# FPGA_DAC.net
KiCad netlist of a schematic drawn in Altium Designer
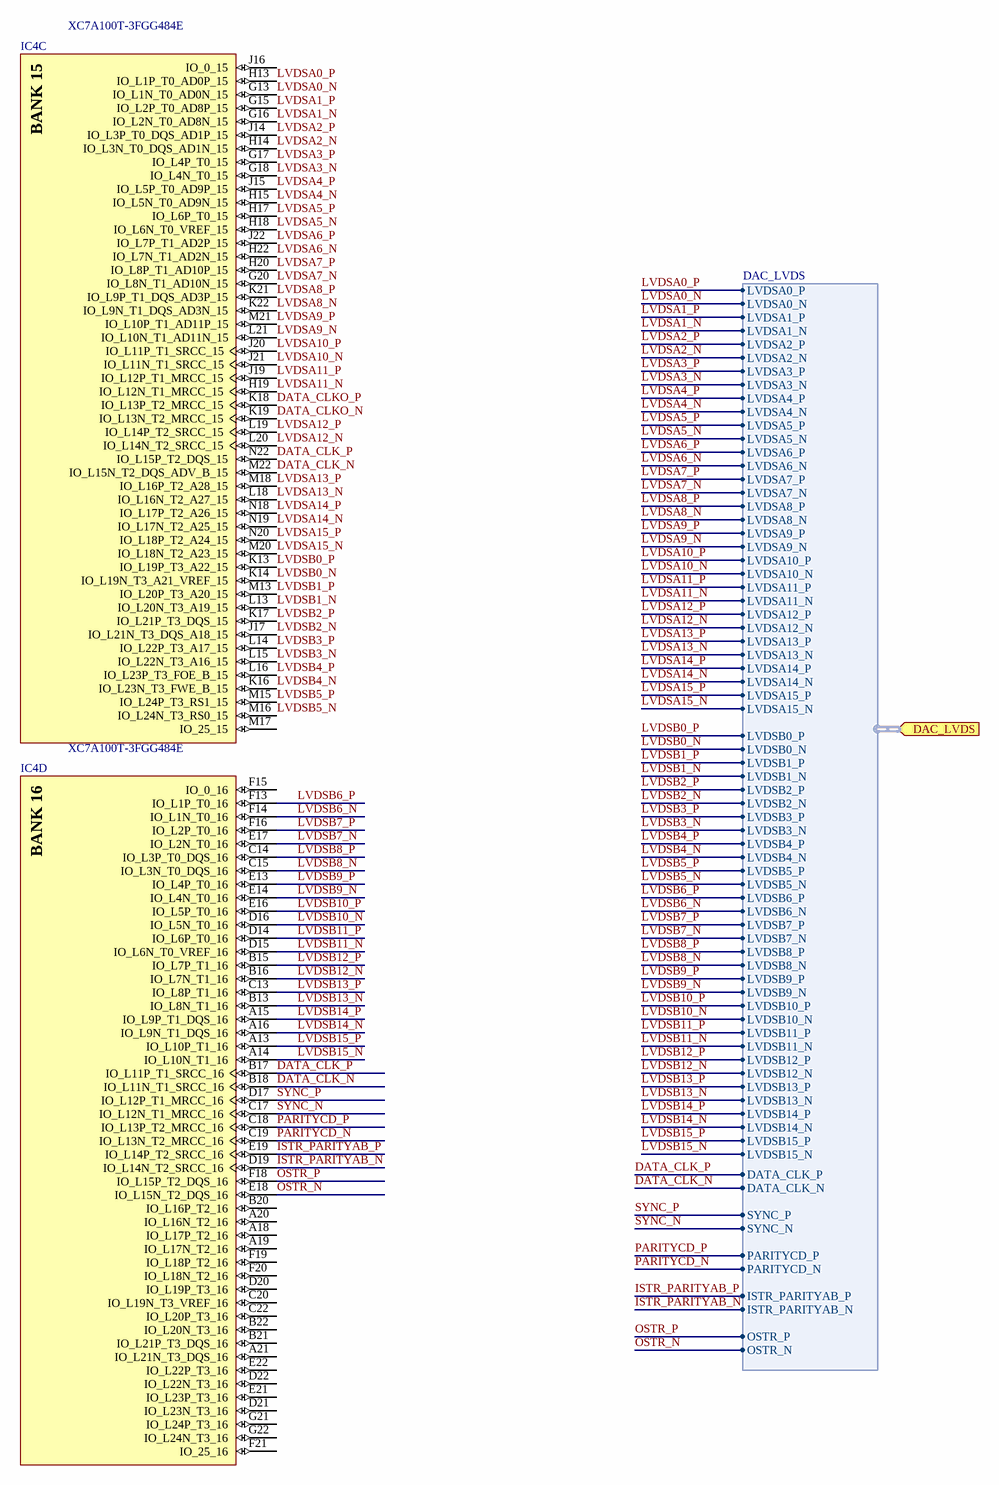
[diagram p0: FPGA_DAC.SchDoc]

(export (version "E")
  (design (tool "Eeschema 10.0.6"))
  (components
    (comp (ref "IC4")
      (value "XC7A100T-3FGG484E")
      (footprint "FGG484")
      (description "Artix-7 FPGA, 285 User I/Os, 4 GTP, 484-Ball BGA, Speed Grade 3, Extended Grade, Pb-Free")
      (fields (field (name "GENERIC PART NUMBER") "XC7A100T") (field (name "MANUFACTURER") "Xilinx"))
      (libsource (lib "Altium Content Vault") (part "XC7A100T-3FGG484E"))
    )
  )
  (nets
    (net (code "2") (name "/DATA_CLKO_N") (class "Default")
      (node (ref "IC4") (pin "K19") (pinfunction "IO_L13N_T2_MRCC_15_K19") (pintype "bidirectional"))
    )
    (net (code "3") (name "/DATA_CLKO_P") (class "Default")
      (node (ref "IC4") (pin "K18") (pinfunction "IO_L13P_T2_MRCC_15_K18") (pintype "bidirectional"))
    )
    (net (code "4") (name "/DATA_CLK_N") (class "Default")
      (node (ref "IC4") (pin "B18") (pinfunction "IO_L11N_T1_SRCC_16_B18") (pintype "bidirectional"))
      (node (ref "IC4") (pin "M22") (pinfunction "IO_L15N_T2_DQS_ADV_B_15_M22") (pintype "bidirectional"))
    )
    (net (code "5") (name "/DATA_CLK_P") (class "Default")
      (node (ref "IC4") (pin "B17") (pinfunction "IO_L11P_T1_SRCC_16_B17") (pintype "bidirectional"))
      (node (ref "IC4") (pin "N22") (pinfunction "IO_L15P_T2_DQS_15_N22") (pintype "bidirectional"))
    )
    (net (code "6") (name "/ISTR_PARITYAB_N") (class "Default")
      (node (ref "IC4") (pin "D19") (pinfunction "IO_L14N_T2_SRCC_16_D19") (pintype "bidirectional"))
    )
    (net (code "7") (name "/ISTR_PARITYAB_P") (class "Default")
      (node (ref "IC4") (pin "E19") (pinfunction "IO_L14P_T2_SRCC_16_E19") (pintype "bidirectional"))
    )
    (net (code "8") (name "/LVDSA0_N") (class "Default")
      (node (ref "IC4") (pin "G13") (pinfunction "IO_L1N_T0_AD0N_15_G13") (pintype "bidirectional"))
    )
    (net (code "9") (name "/LVDSA0_P") (class "Default")
      (node (ref "IC4") (pin "H13") (pinfunction "IO_L1P_T0_AD0P_15_H13") (pintype "bidirectional"))
    )
    (net (code "10") (name "/LVDSA1_N") (class "Default")
      (node (ref "IC4") (pin "G16") (pinfunction "IO_L2N_T0_AD8N_15_G16") (pintype "bidirectional"))
    )
    (net (code "11") (name "/LVDSA1_P") (class "Default")
      (node (ref "IC4") (pin "G15") (pinfunction "IO_L2P_T0_AD8P_15_G15") (pintype "bidirectional"))
    )
    (net (code "12") (name "/LVDSA2_N") (class "Default")
      (node (ref "IC4") (pin "H14") (pinfunction "IO_L3N_T0_DQS_AD1N_15_H14") (pintype "bidirectional"))
    )
    (net (code "13") (name "/LVDSA2_P") (class "Default")
      (node (ref "IC4") (pin "J14") (pinfunction "IO_L3P_T0_DQS_AD1P_15_J14") (pintype "bidirectional"))
    )
    (net (code "14") (name "/LVDSA3_N") (class "Default")
      (node (ref "IC4") (pin "G18") (pinfunction "IO_L4N_T0_15_G18") (pintype "bidirectional"))
    )
    (net (code "15") (name "/LVDSA3_P") (class "Default")
      (node (ref "IC4") (pin "G17") (pinfunction "IO_L4P_T0_15_G17") (pintype "bidirectional"))
    )
    (net (code "16") (name "/LVDSA4_N") (class "Default")
      (node (ref "IC4") (pin "H15") (pinfunction "IO_L5N_T0_AD9N_15_H15") (pintype "bidirectional"))
    )
    (net (code "17") (name "/LVDSA4_P") (class "Default")
      (node (ref "IC4") (pin "J15") (pinfunction "IO_L5P_T0_AD9P_15_J15") (pintype "bidirectional"))
    )
    (net (code "18") (name "/LVDSA5_N") (class "Default")
      (node (ref "IC4") (pin "H18") (pinfunction "IO_L6N_T0_VREF_15_H18") (pintype "bidirectional"))
    )
    (net (code "19") (name "/LVDSA5_P") (class "Default")
      (node (ref "IC4") (pin "H17") (pinfunction "IO_L6P_T0_15_H17") (pintype "bidirectional"))
    )
    (net (code "20") (name "/LVDSA6_N") (class "Default")
      (node (ref "IC4") (pin "H22") (pinfunction "IO_L7N_T1_AD2N_15_H22") (pintype "bidirectional"))
    )
    (net (code "21") (name "/LVDSA6_P") (class "Default")
      (node (ref "IC4") (pin "J22") (pinfunction "IO_L7P_T1_AD2P_15_J22") (pintype "bidirectional"))
    )
    (net (code "22") (name "/LVDSA7_N") (class "Default")
      (node (ref "IC4") (pin "G20") (pinfunction "IO_L8N_T1_AD10N_15_G20") (pintype "bidirectional"))
    )
    (net (code "23") (name "/LVDSA7_P") (class "Default")
      (node (ref "IC4") (pin "H20") (pinfunction "IO_L8P_T1_AD10P_15_H20") (pintype "bidirectional"))
    )
    (net (code "24") (name "/LVDSA8_N") (class "Default")
      (node (ref "IC4") (pin "K22") (pinfunction "IO_L9N_T1_DQS_AD3N_15_K22") (pintype "bidirectional"))
    )
    (net (code "25") (name "/LVDSA8_P") (class "Default")
      (node (ref "IC4") (pin "K21") (pinfunction "IO_L9P_T1_DQS_AD3P_15_K21") (pintype "bidirectional"))
    )
    (net (code "26") (name "/LVDSA9_N") (class "Default")
      (node (ref "IC4") (pin "L21") (pinfunction "IO_L10N_T1_AD11N_15_L21") (pintype "bidirectional"))
    )
    (net (code "27") (name "/LVDSA9_P") (class "Default")
      (node (ref "IC4") (pin "M21") (pinfunction "IO_L10P_T1_AD11P_15_M21") (pintype "bidirectional"))
    )
    (net (code "28") (name "/LVDSA10_N") (class "Default")
      (node (ref "IC4") (pin "J21") (pinfunction "IO_L11N_T1_SRCC_15_J21") (pintype "bidirectional"))
    )
    (net (code "29") (name "/LVDSA10_P") (class "Default")
      (node (ref "IC4") (pin "J20") (pinfunction "IO_L11P_T1_SRCC_15_J20") (pintype "bidirectional"))
    )
    (net (code "30") (name "/LVDSA11_N") (class "Default")
      (node (ref "IC4") (pin "H19") (pinfunction "IO_L12N_T1_MRCC_15_H19") (pintype "bidirectional"))
    )
    (net (code "31") (name "/LVDSA11_P") (class "Default")
      (node (ref "IC4") (pin "J19") (pinfunction "IO_L12P_T1_MRCC_15_J19") (pintype "bidirectional"))
    )
    (net (code "32") (name "/LVDSA12_N") (class "Default")
      (node (ref "IC4") (pin "L20") (pinfunction "IO_L14N_T2_SRCC_15_L20") (pintype "bidirectional"))
    )
    (net (code "33") (name "/LVDSA12_P") (class "Default")
      (node (ref "IC4") (pin "L19") (pinfunction "IO_L14P_T2_SRCC_15_L19") (pintype "bidirectional"))
    )
    (net (code "34") (name "/LVDSA13_N") (class "Default")
      (node (ref "IC4") (pin "L18") (pinfunction "IO_L16N_T2_A27_15_L18") (pintype "bidirectional"))
    )
    (net (code "35") (name "/LVDSA13_P") (class "Default")
      (node (ref "IC4") (pin "M18") (pinfunction "IO_L16P_T2_A28_15_M18") (pintype "bidirectional"))
    )
    (net (code "36") (name "/LVDSA14_N") (class "Default")
      (node (ref "IC4") (pin "N19") (pinfunction "IO_L17N_T2_A25_15_N19") (pintype "bidirectional"))
    )
    (net (code "37") (name "/LVDSA14_P") (class "Default")
      (node (ref "IC4") (pin "N18") (pinfunction "IO_L17P_T2_A26_15_N18") (pintype "bidirectional"))
    )
    (net (code "38") (name "/LVDSA15_N") (class "Default")
      (node (ref "IC4") (pin "M20") (pinfunction "IO_L18N_T2_A23_15_M20") (pintype "bidirectional"))
    )
    (net (code "39") (name "/LVDSA15_P") (class "Default")
      (node (ref "IC4") (pin "N20") (pinfunction "IO_L18P_T2_A24_15_N20") (pintype "bidirectional"))
    )
    (net (code "40") (name "/LVDSB0_N") (class "Default")
      (node (ref "IC4") (pin "K14") (pinfunction "IO_L19N_T3_A21_VREF_15_K14") (pintype "bidirectional"))
    )
    (net (code "41") (name "/LVDSB0_P") (class "Default")
      (node (ref "IC4") (pin "K13") (pinfunction "IO_L19P_T3_A22_15_K13") (pintype "bidirectional"))
    )
    (net (code "42") (name "/LVDSB1_N") (class "Default")
      (node (ref "IC4") (pin "L13") (pinfunction "IO_L20N_T3_A19_15_L13") (pintype "bidirectional"))
    )
    (net (code "43") (name "/LVDSB1_P") (class "Default")
      (node (ref "IC4") (pin "M13") (pinfunction "IO_L20P_T3_A20_15_M13") (pintype "bidirectional"))
    )
    (net (code "44") (name "/LVDSB2_N") (class "Default")
      (node (ref "IC4") (pin "J17") (pinfunction "IO_L21N_T3_DQS_A18_15_J17") (pintype "bidirectional"))
    )
    (net (code "45") (name "/LVDSB2_P") (class "Default")
      (node (ref "IC4") (pin "K17") (pinfunction "IO_L21P_T3_DQS_15_K17") (pintype "bidirectional"))
    )
    (net (code "46") (name "/LVDSB3_N") (class "Default")
      (node (ref "IC4") (pin "L15") (pinfunction "IO_L22N_T3_A16_15_L15") (pintype "bidirectional"))
    )
    (net (code "47") (name "/LVDSB3_P") (class "Default")
      (node (ref "IC4") (pin "L14") (pinfunction "IO_L22P_T3_A17_15_L14") (pintype "bidirectional"))
    )
    (net (code "48") (name "/LVDSB4_N") (class "Default")
      (node (ref "IC4") (pin "K16") (pinfunction "IO_L23N_T3_FWE_B_15_K16") (pintype "bidirectional"))
    )
    (net (code "49") (name "/LVDSB4_P") (class "Default")
      (node (ref "IC4") (pin "L16") (pinfunction "IO_L23P_T3_FOE_B_15_L16") (pintype "bidirectional"))
    )
    (net (code "50") (name "/LVDSB5_N") (class "Default")
      (node (ref "IC4") (pin "M16") (pinfunction "IO_L24N_T3_RS0_15_M16") (pintype "bidirectional"))
    )
    (net (code "51") (name "/LVDSB5_P") (class "Default")
      (node (ref "IC4") (pin "M15") (pinfunction "IO_L24P_T3_RS1_15_M15") (pintype "bidirectional"))
    )
    (net (code "52") (name "/LVDSB6_N") (class "Default")
      (node (ref "IC4") (pin "F14") (pinfunction "IO_L1N_T0_16_F14") (pintype "bidirectional"))
    )
    (net (code "53") (name "/LVDSB6_P") (class "Default")
      (node (ref "IC4") (pin "F13") (pinfunction "IO_L1P_T0_16_F13") (pintype "bidirectional"))
    )
    (net (code "54") (name "/LVDSB7_N") (class "Default")
      (node (ref "IC4") (pin "E17") (pinfunction "IO_L2N_T0_16_E17") (pintype "bidirectional"))
    )
    (net (code "55") (name "/LVDSB7_P") (class "Default")
      (node (ref "IC4") (pin "F16") (pinfunction "IO_L2P_T0_16_F16") (pintype "bidirectional"))
    )
    (net (code "56") (name "/LVDSB8_N") (class "Default")
      (node (ref "IC4") (pin "C15") (pinfunction "IO_L3N_T0_DQS_16_C15") (pintype "bidirectional"))
    )
    (net (code "57") (name "/LVDSB8_P") (class "Default")
      (node (ref "IC4") (pin "C14") (pinfunction "IO_L3P_T0_DQS_16_C14") (pintype "bidirectional"))
    )
    (net (code "58") (name "/LVDSB9_N") (class "Default")
      (node (ref "IC4") (pin "E14") (pinfunction "IO_L4N_T0_16_E14") (pintype "bidirectional"))
    )
    (net (code "59") (name "/LVDSB9_P") (class "Default")
      (node (ref "IC4") (pin "E13") (pinfunction "IO_L4P_T0_16_E13") (pintype "bidirectional"))
    )
    (net (code "60") (name "/LVDSB10_N") (class "Default")
      (node (ref "IC4") (pin "D16") (pinfunction "IO_L5N_T0_16_D16") (pintype "bidirectional"))
    )
    (net (code "61") (name "/LVDSB10_P") (class "Default")
      (node (ref "IC4") (pin "E16") (pinfunction "IO_L5P_T0_16_E16") (pintype "bidirectional"))
    )
    (net (code "62") (name "/LVDSB11_N") (class "Default")
      (node (ref "IC4") (pin "D15") (pinfunction "IO_L6N_T0_VREF_16_D15") (pintype "bidirectional"))
    )
    (net (code "63") (name "/LVDSB11_P") (class "Default")
      (node (ref "IC4") (pin "D14") (pinfunction "IO_L6P_T0_16_D14") (pintype "bidirectional"))
    )
    (net (code "64") (name "/LVDSB12_N") (class "Default")
      (node (ref "IC4") (pin "B16") (pinfunction "IO_L7N_T1_16_B16") (pintype "bidirectional"))
    )
    (net (code "65") (name "/LVDSB12_P") (class "Default")
      (node (ref "IC4") (pin "B15") (pinfunction "IO_L7P_T1_16_B15") (pintype "bidirectional"))
    )
    (net (code "66") (name "/LVDSB13_N") (class "Default")
      (node (ref "IC4") (pin "B13") (pinfunction "IO_L8N_T1_16_B13") (pintype "bidirectional"))
    )
    (net (code "67") (name "/LVDSB13_P") (class "Default")
      (node (ref "IC4") (pin "C13") (pinfunction "IO_L8P_T1_16_C13") (pintype "bidirectional"))
    )
    (net (code "68") (name "/LVDSB14_N") (class "Default")
      (node (ref "IC4") (pin "A16") (pinfunction "IO_L9N_T1_DQS_16_A16") (pintype "bidirectional"))
    )
    (net (code "69") (name "/LVDSB14_P") (class "Default")
      (node (ref "IC4") (pin "A15") (pinfunction "IO_L9P_T1_DQS_16_A15") (pintype "bidirectional"))
    )
    (net (code "70") (name "/LVDSB15_N") (class "Default")
      (node (ref "IC4") (pin "A14") (pinfunction "IO_L10N_T1_16_A14") (pintype "bidirectional"))
    )
    (net (code "71") (name "/LVDSB15_P") (class "Default")
      (node (ref "IC4") (pin "A13") (pinfunction "IO_L10P_T1_16_A13") (pintype "bidirectional"))
    )
    (net (code "72") (name "/OSTR_N") (class "Default")
      (node (ref "IC4") (pin "E18") (pinfunction "IO_L15N_T2_DQS_16_E18") (pintype "bidirectional"))
    )
    (net (code "73") (name "/OSTR_P") (class "Default")
      (node (ref "IC4") (pin "F18") (pinfunction "IO_L15P_T2_DQS_16_F18") (pintype "bidirectional"))
    )
    (net (code "74") (name "/PARITYCD_N") (class "Default")
      (node (ref "IC4") (pin "C19") (pinfunction "IO_L13N_T2_MRCC_16_C19") (pintype "bidirectional"))
    )
    (net (code "75") (name "/PARITYCD_P") (class "Default")
      (node (ref "IC4") (pin "C18") (pinfunction "IO_L13P_T2_MRCC_16_C18") (pintype "bidirectional"))
    )
    (net (code "76") (name "/SYNC_N") (class "Default")
      (node (ref "IC4") (pin "C17") (pinfunction "IO_L12N_T1_MRCC_16_C17") (pintype "bidirectional"))
    )
    (net (code "77") (name "/SYNC_P") (class "Default")
      (node (ref "IC4") (pin "D17") (pinfunction "IO_L12P_T1_MRCC_16_D17") (pintype "bidirectional"))
    )
    (net (code "79") (name "unconnected-(IC4C-IO_0_15-PadJ16)") (class "Default")
      (node (ref "IC4") (pin "J16") (pinfunction "IO_0_15_J16") (pintype "bidirectional"))
    )
    (net (code "80") (name "unconnected-(IC4C-IO_25_15-PadM17)") (class "Default")
      (node (ref "IC4") (pin "M17") (pinfunction "IO_25_15_M17") (pintype "bidirectional"))
    )
    (net (code "81") (name "unconnected-(IC4D-IO_0_16-PadF15)") (class "Default")
      (node (ref "IC4") (pin "F15") (pinfunction "IO_0_16_F15") (pintype "bidirectional"))
    )
    (net (code "82") (name "unconnected-(IC4D-IO_25_16-PadF21)") (class "Default")
      (node (ref "IC4") (pin "F21") (pinfunction "IO_25_16_F21") (pintype "bidirectional"))
    )
    (net (code "83") (name "unconnected-(IC4D-IO_L16N_T2_16-PadA20)") (class "Default")
      (node (ref "IC4") (pin "A20") (pinfunction "IO_L16N_T2_16_A20") (pintype "bidirectional"))
    )
    (net (code "84") (name "unconnected-(IC4D-IO_L16P_T2_16-PadB20)") (class "Default")
      (node (ref "IC4") (pin "B20") (pinfunction "IO_L16P_T2_16_B20") (pintype "bidirectional"))
    )
    (net (code "85") (name "unconnected-(IC4D-IO_L17N_T2_16-PadA19)") (class "Default")
      (node (ref "IC4") (pin "A19") (pinfunction "IO_L17N_T2_16_A19") (pintype "bidirectional"))
    )
    (net (code "86") (name "unconnected-(IC4D-IO_L17P_T2_16-PadA18)") (class "Default")
      (node (ref "IC4") (pin "A18") (pinfunction "IO_L17P_T2_16_A18") (pintype "bidirectional"))
    )
    (net (code "87") (name "unconnected-(IC4D-IO_L18N_T2_16-PadF20)") (class "Default")
      (node (ref "IC4") (pin "F20") (pinfunction "IO_L18N_T2_16_F20") (pintype "bidirectional"))
    )
    (net (code "88") (name "unconnected-(IC4D-IO_L18P_T2_16-PadF19)") (class "Default")
      (node (ref "IC4") (pin "F19") (pinfunction "IO_L18P_T2_16_F19") (pintype "bidirectional"))
    )
    (net (code "89") (name "unconnected-(IC4D-IO_L19N_T3_VREF_16-PadC20)") (class "Default")
      (node (ref "IC4") (pin "C20") (pinfunction "IO_L19N_T3_VREF_16_C20") (pintype "bidirectional"))
    )
    (net (code "90") (name "unconnected-(IC4D-IO_L19P_T3_16-PadD20)") (class "Default")
      (node (ref "IC4") (pin "D20") (pinfunction "IO_L19P_T3_16_D20") (pintype "bidirectional"))
    )
    (net (code "91") (name "unconnected-(IC4D-IO_L20N_T3_16-PadB22)") (class "Default")
      (node (ref "IC4") (pin "B22") (pinfunction "IO_L20N_T3_16_B22") (pintype "bidirectional"))
    )
    (net (code "92") (name "unconnected-(IC4D-IO_L20P_T3_16-PadC22)") (class "Default")
      (node (ref "IC4") (pin "C22") (pinfunction "IO_L20P_T3_16_C22") (pintype "bidirectional"))
    )
    (net (code "93") (name "unconnected-(IC4D-IO_L21N_T3_DQS_16-PadA21)") (class "Default")
      (node (ref "IC4") (pin "A21") (pinfunction "IO_L21N_T3_DQS_16_A21") (pintype "bidirectional"))
    )
    (net (code "94") (name "unconnected-(IC4D-IO_L21P_T3_DQS_16-PadB21)") (class "Default")
      (node (ref "IC4") (pin "B21") (pinfunction "IO_L21P_T3_DQS_16_B21") (pintype "bidirectional"))
    )
    (net (code "95") (name "unconnected-(IC4D-IO_L22N_T3_16-PadD22)") (class "Default")
      (node (ref "IC4") (pin "D22") (pinfunction "IO_L22N_T3_16_D22") (pintype "bidirectional"))
    )
    (net (code "96") (name "unconnected-(IC4D-IO_L22P_T3_16-PadE22)") (class "Default")
      (node (ref "IC4") (pin "E22") (pinfunction "IO_L22P_T3_16_E22") (pintype "bidirectional"))
    )
    (net (code "97") (name "unconnected-(IC4D-IO_L23N_T3_16-PadD21)") (class "Default")
      (node (ref "IC4") (pin "D21") (pinfunction "IO_L23N_T3_16_D21") (pintype "bidirectional"))
    )
    (net (code "98") (name "unconnected-(IC4D-IO_L23P_T3_16-PadE21)") (class "Default")
      (node (ref "IC4") (pin "E21") (pinfunction "IO_L23P_T3_16_E21") (pintype "bidirectional"))
    )
    (net (code "99") (name "unconnected-(IC4D-IO_L24N_T3_16-PadG22)") (class "Default")
      (node (ref "IC4") (pin "G22") (pinfunction "IO_L24N_T3_16_G22") (pintype "bidirectional"))
    )
    (net (code "100") (name "unconnected-(IC4D-IO_L24P_T3_16-PadG21)") (class "Default")
      (node (ref "IC4") (pin "G21") (pinfunction "IO_L24P_T3_16_G21") (pintype "bidirectional"))
    )
  )
)
